# shield.net
KiCad netlist of a schematic drawn in EAGLE
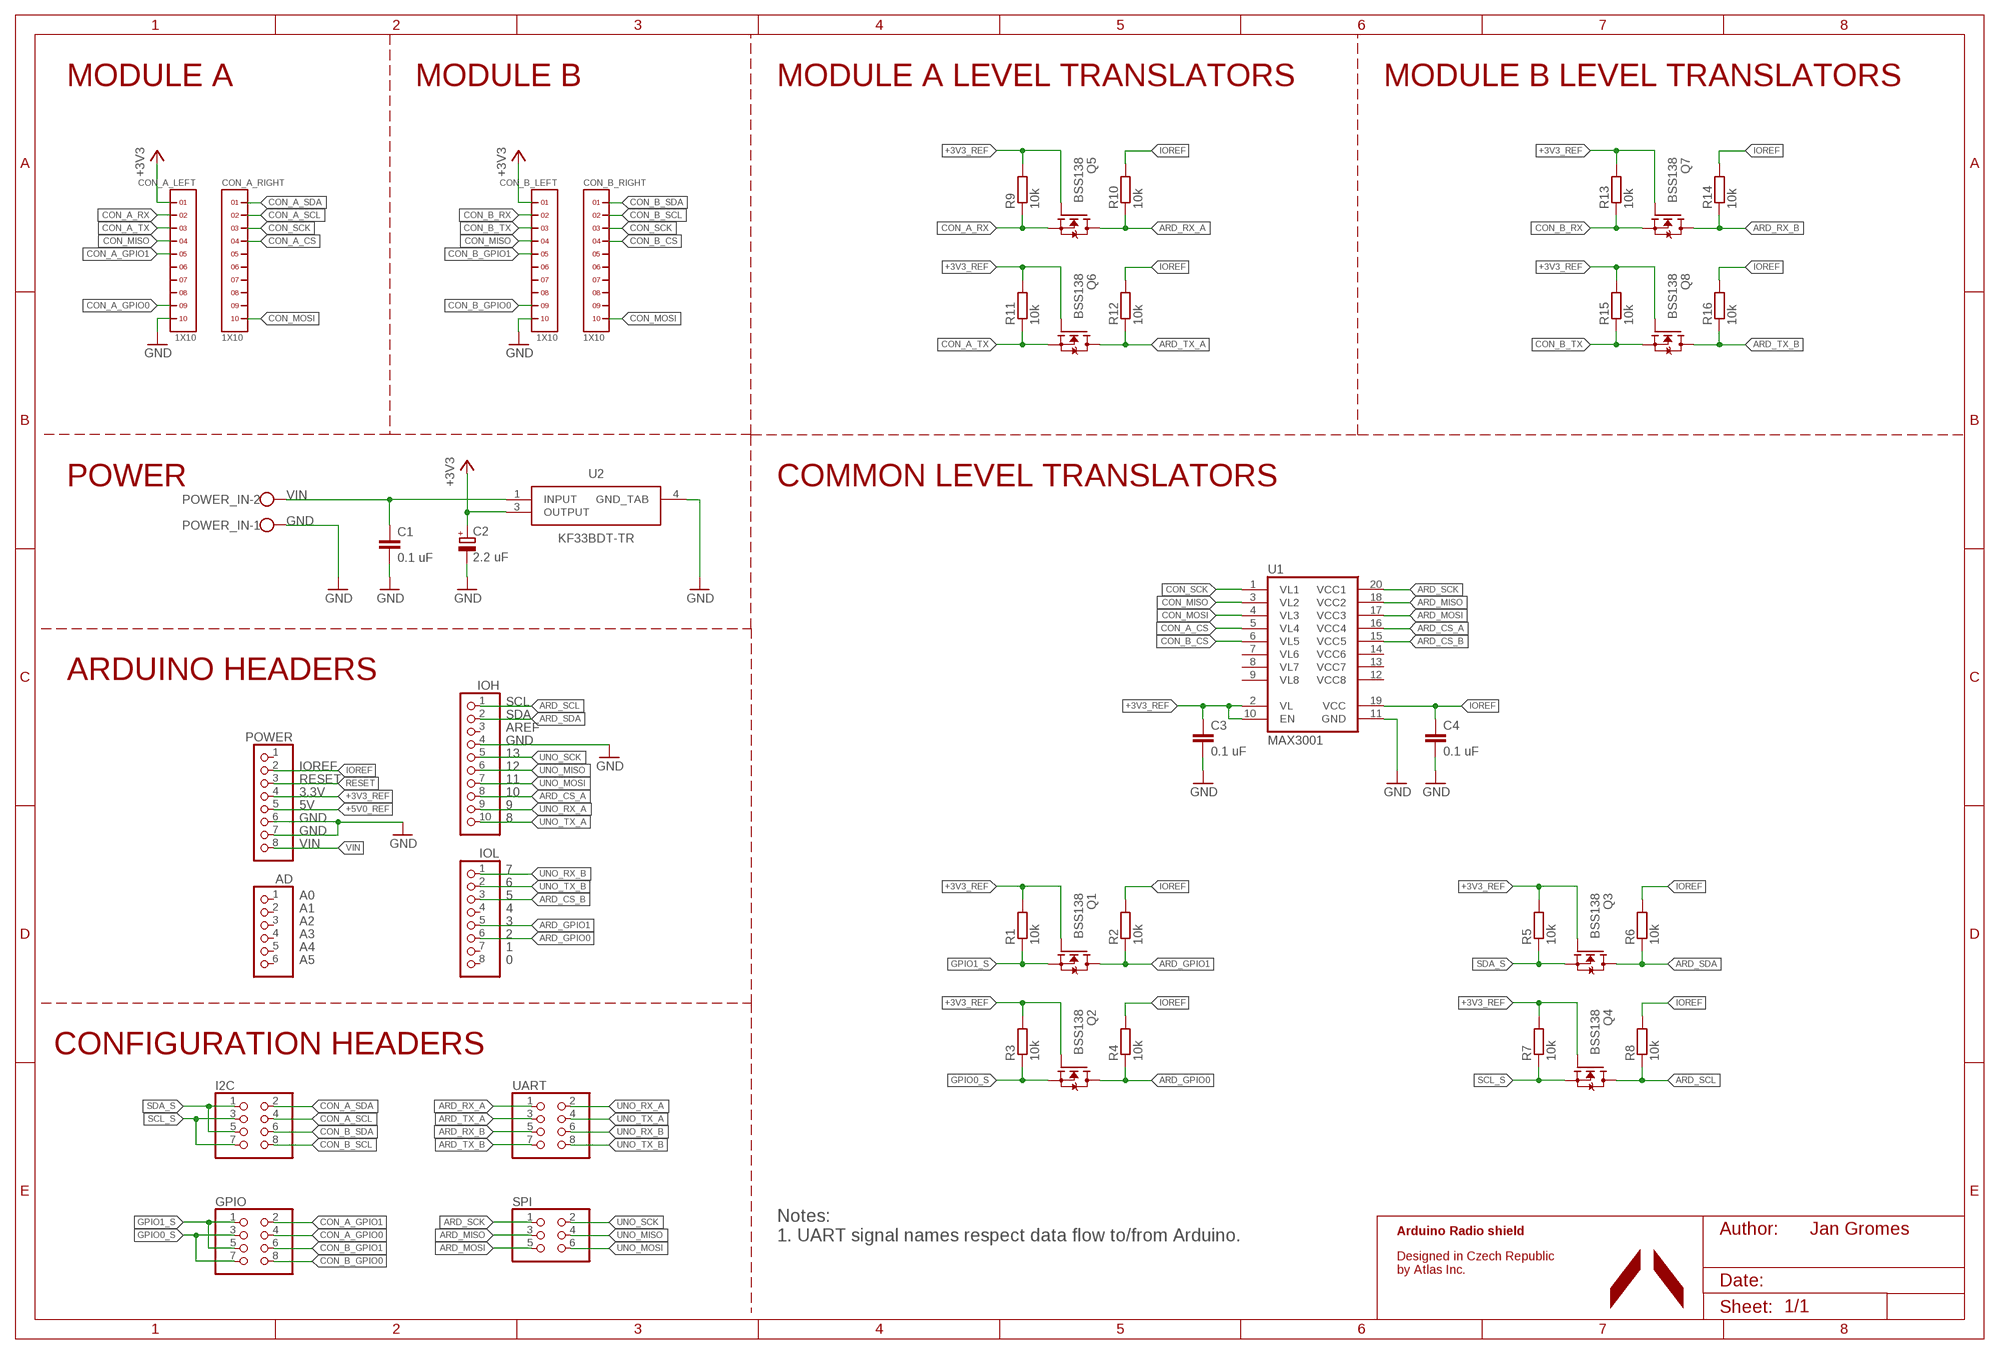
[diagram p0: schematic, sheet 1]

(export (version "E")
  (design (tool "Eeschema 10.0.6"))
  (components
    (comp (ref "AD")
      (value "PINHD-1X6")
      (footprint "eagle-import:1X06")
      (libsource (lib "eagle-import") (part "PINHD-1X6"))
    )
    (comp (ref "C1")
      (value "0.1 uF")
      (footprint "eagle-import:C0603")
      (libsource (lib "eagle-import") (part "C-EUC0603"))
    )
    (comp (ref "C2")
      (value "2.2 uF")
      (footprint "eagle-import:SMC_A")
      (libsource (lib "eagle-import") (part "CPOL-EUSMCA"))
    )
    (comp (ref "C3")
      (value "0.1 uF")
      (footprint "eagle-import:C0603")
      (libsource (lib "eagle-import") (part "C-EUC0603"))
    )
    (comp (ref "C4")
      (value "0.1 uF")
      (footprint "eagle-import:C0603")
      (libsource (lib "eagle-import") (part "C-EUC0603"))
    )
    (comp (ref "CON_A_LEFT")
      (value "1X10")
      (footprint "eagle-import:1X10")
      (libsource (lib "eagle-import") (part "1X10"))
    )
    (comp (ref "CON_A_RIGHT")
      (value "1X10")
      (footprint "eagle-import:1X10")
      (libsource (lib "eagle-import") (part "1X10"))
    )
    (comp (ref "CON_B_LEFT")
      (value "1X10")
      (footprint "eagle-import:1X10")
      (libsource (lib "eagle-import") (part "1X10"))
    )
    (comp (ref "CON_B_RIGHT")
      (value "1X10")
      (footprint "eagle-import:1X10")
      (libsource (lib "eagle-import") (part "1X10"))
    )
    (comp (ref "GPIO")
      (value "PINHD-2X4")
      (footprint "eagle-import:2X04")
      (libsource (lib "eagle-import") (part "PINHD-2X4"))
    )
    (comp (ref "I2C")
      (value "PINHD-2X4")
      (footprint "eagle-import:2X04")
      (libsource (lib "eagle-import") (part "PINHD-2X4"))
    )
    (comp (ref "IOH")
      (value "PINHD-1X10")
      (footprint "eagle-import:1X10")
      (libsource (lib "eagle-import") (part "PINHD-1X10"))
    )
    (comp (ref "IOL")
      (value "PINHD-1X8")
      (footprint "eagle-import:1X08")
      (libsource (lib "eagle-import") (part "PINHD-1X8"))
    )
    (comp (ref "POWER")
      (value "PINHD-1X8")
      (footprint "eagle-import:1X08")
      (libsource (lib "eagle-import") (part "PINHD-1X8"))
    )
    (comp (ref "POWER_IN")
      (value "W237-102")
      (footprint "eagle-import:W237-102")
      (fields (field (name "MPN") "237-102"))
      (libsource (lib "eagle-import") (part "W237-102"))
    )
    (comp (ref "Q1")
      (value "BSS138")
      (footprint "eagle-import:SOT23")
      (fields (field (name "MF") "Fairchild"))
      (libsource (lib "eagle-import") (part "BSS138"))
    )
    (comp (ref "Q2")
      (value "BSS138")
      (footprint "eagle-import:SOT23")
      (fields (field (name "MF") "Fairchild"))
      (libsource (lib "eagle-import") (part "BSS138"))
    )
    (comp (ref "Q3")
      (value "BSS138")
      (footprint "eagle-import:SOT23")
      (fields (field (name "MF") "Fairchild"))
      (libsource (lib "eagle-import") (part "BSS138"))
    )
    (comp (ref "Q4")
      (value "BSS138")
      (footprint "eagle-import:SOT23")
      (fields (field (name "MF") "Fairchild"))
      (libsource (lib "eagle-import") (part "BSS138"))
    )
    (comp (ref "Q5")
      (value "BSS138")
      (footprint "eagle-import:SOT23")
      (fields (field (name "MF") "Fairchild"))
      (libsource (lib "eagle-import") (part "BSS138"))
    )
    (comp (ref "Q6")
      (value "BSS138")
      (footprint "eagle-import:SOT23")
      (fields (field (name "MF") "Fairchild"))
      (libsource (lib "eagle-import") (part "BSS138"))
    )
    (comp (ref "Q7")
      (value "BSS138")
      (footprint "eagle-import:SOT23")
      (fields (field (name "MF") "Fairchild"))
      (libsource (lib "eagle-import") (part "BSS138"))
    )
    (comp (ref "Q8")
      (value "BSS138")
      (footprint "eagle-import:SOT23")
      (fields (field (name "MF") "Fairchild"))
      (libsource (lib "eagle-import") (part "BSS138"))
    )
    (comp (ref "R1")
      (value "10k")
      (footprint "eagle-import:R0603")
      (libsource (lib "eagle-import") (part "R-EU_R0603"))
    )
    (comp (ref "R2")
      (value "10k")
      (footprint "eagle-import:R0603")
      (libsource (lib "eagle-import") (part "R-EU_R0603"))
    )
    (comp (ref "R3")
      (value "10k")
      (footprint "eagle-import:R0603")
      (libsource (lib "eagle-import") (part "R-EU_R0603"))
    )
    (comp (ref "R4")
      (value "10k")
      (footprint "eagle-import:R0603")
      (libsource (lib "eagle-import") (part "R-EU_R0603"))
    )
    (comp (ref "R5")
      (value "10k")
      (footprint "eagle-import:R0603")
      (libsource (lib "eagle-import") (part "R-EU_R0603"))
    )
    (comp (ref "R6")
      (value "10k")
      (footprint "eagle-import:R0603")
      (libsource (lib "eagle-import") (part "R-EU_R0603"))
    )
    (comp (ref "R7")
      (value "10k")
      (footprint "eagle-import:R0603")
      (libsource (lib "eagle-import") (part "R-EU_R0603"))
    )
    (comp (ref "R8")
      (value "10k")
      (footprint "eagle-import:R0603")
      (libsource (lib "eagle-import") (part "R-EU_R0603"))
    )
    (comp (ref "R9")
      (value "10k")
      (footprint "eagle-import:R0603")
      (libsource (lib "eagle-import") (part "R-EU_R0603"))
    )
    (comp (ref "R10")
      (value "10k")
      (footprint "eagle-import:R0603")
      (libsource (lib "eagle-import") (part "R-EU_R0603"))
    )
    (comp (ref "R11")
      (value "10k")
      (footprint "eagle-import:R0603")
      (libsource (lib "eagle-import") (part "R-EU_R0603"))
    )
    (comp (ref "R12")
      (value "10k")
      (footprint "eagle-import:R0603")
      (libsource (lib "eagle-import") (part "R-EU_R0603"))
    )
    (comp (ref "R13")
      (value "10k")
      (footprint "eagle-import:R0603")
      (libsource (lib "eagle-import") (part "R-EU_R0603"))
    )
    (comp (ref "R14")
      (value "10k")
      (footprint "eagle-import:R0603")
      (libsource (lib "eagle-import") (part "R-EU_R0603"))
    )
    (comp (ref "R15")
      (value "10k")
      (footprint "eagle-import:R0603")
      (libsource (lib "eagle-import") (part "R-EU_R0603"))
    )
    (comp (ref "R16")
      (value "10k")
      (footprint "eagle-import:R0603")
      (libsource (lib "eagle-import") (part "R-EU_R0603"))
    )
    (comp (ref "SPI")
      (value "PINHD-2X3")
      (footprint "eagle-import:2X03")
      (libsource (lib "eagle-import") (part "PINHD-2X3"))
    )
    (comp (ref "U1")
      (value "MAX3001")
      (footprint "eagle-import:TSSOP20")
      (libsource (lib "eagle-import") (part "MAX3001"))
    )
    (comp (ref "U2")
      (value "KF33BDT-TR")
      (footprint "eagle-import:TO228P972X240-3N")
      (fields (field (name "RS_PART_NUMBER") "7140616"))
      (libsource (lib "eagle-import") (part "KF33BDT-TR"))
    )
    (comp (ref "UART")
      (value "PINHD-2X4")
      (footprint "eagle-import:2X04")
      (libsource (lib "eagle-import") (part "PINHD-2X4"))
    )
  )
  (nets
    (net (code "1") (name "+3V3") (class "Default")
      (node (ref "C2") (pin "+") (pinfunction "+_+") (pintype "passive"))
      (node (ref "CON_A_LEFT") (pin "1") (pinfunction "1_1") (pintype "bidirectional"))
      (node (ref "CON_B_LEFT") (pin "1") (pinfunction "1_1") (pintype "bidirectional"))
      (node (ref "U2") (pin "3") (pinfunction "OUTPUT_3") (pintype "output"))
    )
    (net (code "2") (name "+3V3_REF") (class "Default")
      (node (ref "C3") (pin "1") (pinfunction "1_1") (pintype "passive"))
      (node (ref "POWER") (pin "4") (pinfunction "4_4") (pintype "passive"))
      (node (ref "Q1") (pin "1") (pinfunction "G_1") (pintype "passive"))
      (node (ref "Q2") (pin "1") (pinfunction "G_1") (pintype "passive"))
      (node (ref "Q3") (pin "1") (pinfunction "G_1") (pintype "passive"))
      (node (ref "Q4") (pin "1") (pinfunction "G_1") (pintype "passive"))
      (node (ref "Q5") (pin "1") (pinfunction "G_1") (pintype "passive"))
      (node (ref "Q6") (pin "1") (pinfunction "G_1") (pintype "passive"))
      (node (ref "Q7") (pin "1") (pinfunction "G_1") (pintype "passive"))
      (node (ref "Q8") (pin "1") (pinfunction "G_1") (pintype "passive"))
      (node (ref "R1") (pin "2") (pinfunction "2_2") (pintype "passive"))
      (node (ref "R11") (pin "2") (pinfunction "2_2") (pintype "passive"))
      (node (ref "R13") (pin "2") (pinfunction "2_2") (pintype "passive"))
      (node (ref "R15") (pin "2") (pinfunction "2_2") (pintype "passive"))
      (node (ref "R3") (pin "2") (pinfunction "2_2") (pintype "passive"))
      (node (ref "R5") (pin "2") (pinfunction "2_2") (pintype "passive"))
      (node (ref "R7") (pin "2") (pinfunction "2_2") (pintype "passive"))
      (node (ref "R9") (pin "2") (pinfunction "2_2") (pintype "passive"))
      (node (ref "U1") (pin "10") (pinfunction "EN_10") (pintype "power_in"))
      (node (ref "U1") (pin "2") (pinfunction "VL_2") (pintype "input"))
    )
    (net (code "3") (name "+5V0_REF") (class "Default")
      (node (ref "POWER") (pin "5") (pinfunction "5_5") (pintype "passive"))
    )
    (net (code "4") (name "ARD_CS_A") (class "Default")
      (node (ref "IOH") (pin "8") (pinfunction "8_8") (pintype "passive"))
      (node (ref "U1") (pin "16") (pinfunction "VCC4_16") (pintype "bidirectional"))
    )
    (net (code "5") (name "ARD_CS_B") (class "Default")
      (node (ref "IOL") (pin "3") (pinfunction "3_3") (pintype "passive"))
      (node (ref "U1") (pin "15") (pinfunction "VCC5_15") (pintype "bidirectional"))
    )
    (net (code "6") (name "ARD_GPIO0") (class "Default")
      (node (ref "IOL") (pin "6") (pinfunction "6_6") (pintype "passive"))
      (node (ref "Q2") (pin "3") (pinfunction "D_3") (pintype "passive"))
      (node (ref "R4") (pin "1") (pinfunction "1_1") (pintype "passive"))
    )
    (net (code "7") (name "ARD_GPIO1") (class "Default")
      (node (ref "IOL") (pin "5") (pinfunction "5_5") (pintype "passive"))
      (node (ref "Q1") (pin "3") (pinfunction "D_3") (pintype "passive"))
      (node (ref "R2") (pin "1") (pinfunction "1_1") (pintype "passive"))
    )
    (net (code "8") (name "ARD_MISO") (class "Default")
      (node (ref "SPI") (pin "3") (pinfunction "3_3") (pintype "passive"))
      (node (ref "U1") (pin "18") (pinfunction "VCC2_18") (pintype "bidirectional"))
    )
    (net (code "9") (name "ARD_MOSI") (class "Default")
      (node (ref "SPI") (pin "5") (pinfunction "5_5") (pintype "passive"))
      (node (ref "U1") (pin "17") (pinfunction "VCC3_17") (pintype "bidirectional"))
    )
    (net (code "10") (name "ARD_RX_A") (class "Default")
      (node (ref "Q5") (pin "3") (pinfunction "D_3") (pintype "passive"))
      (node (ref "R10") (pin "1") (pinfunction "1_1") (pintype "passive"))
      (node (ref "UART") (pin "1") (pinfunction "1_1") (pintype "passive"))
    )
    (net (code "11") (name "ARD_RX_B") (class "Default")
      (node (ref "Q7") (pin "3") (pinfunction "D_3") (pintype "passive"))
      (node (ref "R14") (pin "1") (pinfunction "1_1") (pintype "passive"))
      (node (ref "UART") (pin "5") (pinfunction "5_5") (pintype "passive"))
    )
    (net (code "12") (name "ARD_SCK") (class "Default")
      (node (ref "SPI") (pin "1") (pinfunction "1_1") (pintype "passive"))
      (node (ref "U1") (pin "20") (pinfunction "VCC1_20") (pintype "bidirectional"))
    )
    (net (code "13") (name "ARD_SCL") (class "Default")
      (node (ref "IOH") (pin "1") (pinfunction "1_1") (pintype "passive"))
      (node (ref "Q4") (pin "3") (pinfunction "D_3") (pintype "passive"))
      (node (ref "R8") (pin "1") (pinfunction "1_1") (pintype "passive"))
    )
    (net (code "14") (name "ARD_SDA") (class "Default")
      (node (ref "IOH") (pin "2") (pinfunction "2_2") (pintype "passive"))
      (node (ref "Q3") (pin "3") (pinfunction "D_3") (pintype "passive"))
      (node (ref "R6") (pin "1") (pinfunction "1_1") (pintype "passive"))
    )
    (net (code "15") (name "ARD_TX_A") (class "Default")
      (node (ref "Q6") (pin "3") (pinfunction "D_3") (pintype "passive"))
      (node (ref "R12") (pin "1") (pinfunction "1_1") (pintype "passive"))
      (node (ref "UART") (pin "3") (pinfunction "3_3") (pintype "passive"))
    )
    (net (code "16") (name "ARD_TX_B") (class "Default")
      (node (ref "Q8") (pin "3") (pinfunction "D_3") (pintype "passive"))
      (node (ref "R16") (pin "1") (pinfunction "1_1") (pintype "passive"))
      (node (ref "UART") (pin "7") (pinfunction "7_7") (pintype "passive"))
    )
    (net (code "17") (name "CON_A_CS") (class "Default")
      (node (ref "CON_A_RIGHT") (pin "4") (pinfunction "4_4") (pintype "bidirectional"))
      (node (ref "U1") (pin "5") (pinfunction "VL4_5") (pintype "bidirectional"))
    )
    (net (code "18") (name "CON_A_GPIO0") (class "Default")
      (node (ref "CON_A_LEFT") (pin "9") (pinfunction "9_9") (pintype "bidirectional"))
      (node (ref "GPIO") (pin "4") (pinfunction "4_4") (pintype "passive"))
    )
    (net (code "19") (name "CON_A_GPIO1") (class "Default")
      (node (ref "CON_A_LEFT") (pin "5") (pinfunction "5_5") (pintype "bidirectional"))
      (node (ref "GPIO") (pin "2") (pinfunction "2_2") (pintype "passive"))
    )
    (net (code "20") (name "CON_A_RX") (class "Default")
      (node (ref "CON_A_LEFT") (pin "2") (pinfunction "2_2") (pintype "bidirectional"))
      (node (ref "Q5") (pin "2") (pinfunction "S_2") (pintype "passive"))
      (node (ref "R9") (pin "1") (pinfunction "1_1") (pintype "passive"))
    )
    (net (code "21") (name "CON_A_SCL") (class "Default")
      (node (ref "CON_A_RIGHT") (pin "2") (pinfunction "2_2") (pintype "bidirectional"))
      (node (ref "I2C") (pin "4") (pinfunction "4_4") (pintype "passive"))
    )
    (net (code "22") (name "CON_A_SDA") (class "Default")
      (node (ref "CON_A_RIGHT") (pin "1") (pinfunction "1_1") (pintype "bidirectional"))
      (node (ref "I2C") (pin "2") (pinfunction "2_2") (pintype "passive"))
    )
    (net (code "23") (name "CON_A_TX") (class "Default")
      (node (ref "CON_A_LEFT") (pin "3") (pinfunction "3_3") (pintype "bidirectional"))
      (node (ref "Q6") (pin "2") (pinfunction "S_2") (pintype "passive"))
      (node (ref "R11") (pin "1") (pinfunction "1_1") (pintype "passive"))
    )
    (net (code "24") (name "CON_B_CS") (class "Default")
      (node (ref "CON_B_RIGHT") (pin "4") (pinfunction "4_4") (pintype "bidirectional"))
      (node (ref "U1") (pin "6") (pinfunction "VL5_6") (pintype "bidirectional"))
    )
    (net (code "25") (name "CON_B_GPIO0") (class "Default")
      (node (ref "CON_B_LEFT") (pin "9") (pinfunction "9_9") (pintype "bidirectional"))
      (node (ref "GPIO") (pin "8") (pinfunction "8_8") (pintype "passive"))
    )
    (net (code "26") (name "CON_B_GPIO1") (class "Default")
      (node (ref "CON_B_LEFT") (pin "5") (pinfunction "5_5") (pintype "bidirectional"))
      (node (ref "GPIO") (pin "6") (pinfunction "6_6") (pintype "passive"))
    )
    (net (code "27") (name "CON_B_RX") (class "Default")
      (node (ref "CON_B_LEFT") (pin "2") (pinfunction "2_2") (pintype "bidirectional"))
      (node (ref "Q7") (pin "2") (pinfunction "S_2") (pintype "passive"))
      (node (ref "R13") (pin "1") (pinfunction "1_1") (pintype "passive"))
    )
    (net (code "28") (name "CON_B_SCL") (class "Default")
      (node (ref "CON_B_RIGHT") (pin "2") (pinfunction "2_2") (pintype "bidirectional"))
      (node (ref "I2C") (pin "8") (pinfunction "8_8") (pintype "passive"))
    )
    (net (code "29") (name "CON_B_SDA") (class "Default")
      (node (ref "CON_B_RIGHT") (pin "1") (pinfunction "1_1") (pintype "bidirectional"))
      (node (ref "I2C") (pin "6") (pinfunction "6_6") (pintype "passive"))
    )
    (net (code "30") (name "CON_B_TX") (class "Default")
      (node (ref "CON_B_LEFT") (pin "3") (pinfunction "3_3") (pintype "bidirectional"))
      (node (ref "Q8") (pin "2") (pinfunction "S_2") (pintype "passive"))
      (node (ref "R15") (pin "1") (pinfunction "1_1") (pintype "passive"))
    )
    (net (code "31") (name "CON_MISO") (class "Default")
      (node (ref "CON_A_LEFT") (pin "4") (pinfunction "4_4") (pintype "bidirectional"))
      (node (ref "CON_B_LEFT") (pin "4") (pinfunction "4_4") (pintype "bidirectional"))
      (node (ref "U1") (pin "3") (pinfunction "VL2_3") (pintype "bidirectional"))
    )
    (net (code "32") (name "CON_MOSI") (class "Default")
      (node (ref "CON_A_RIGHT") (pin "10") (pinfunction "10_10") (pintype "bidirectional"))
      (node (ref "CON_B_RIGHT") (pin "10") (pinfunction "10_10") (pintype "bidirectional"))
      (node (ref "U1") (pin "4") (pinfunction "VL3_4") (pintype "bidirectional"))
    )
    (net (code "33") (name "CON_SCK") (class "Default")
      (node (ref "CON_A_RIGHT") (pin "3") (pinfunction "3_3") (pintype "bidirectional"))
      (node (ref "CON_B_RIGHT") (pin "3") (pinfunction "3_3") (pintype "bidirectional"))
      (node (ref "U1") (pin "1") (pinfunction "VL1_1") (pintype "bidirectional"))
    )
    (net (code "34") (name "GND") (class "Default")
      (node (ref "C1") (pin "2") (pinfunction "2_2") (pintype "passive"))
      (node (ref "C2") (pin "-") (pinfunction "-_-") (pintype "passive"))
      (node (ref "C3") (pin "2") (pinfunction "2_2") (pintype "passive"))
      (node (ref "C4") (pin "2") (pinfunction "2_2") (pintype "passive"))
      (node (ref "CON_A_LEFT") (pin "10") (pinfunction "10_10") (pintype "bidirectional"))
      (node (ref "CON_B_LEFT") (pin "10") (pinfunction "10_10") (pintype "bidirectional"))
      (node (ref "IOH") (pin "4") (pinfunction "4_4") (pintype "passive"))
      (node (ref "POWER") (pin "6") (pinfunction "6_6") (pintype "passive"))
      (node (ref "POWER") (pin "7") (pinfunction "7_7") (pintype "passive"))
      (node (ref "POWER_IN") (pin "1") (pinfunction "KL_1") (pintype "passive"))
      (node (ref "U1") (pin "11") (pinfunction "GND_11") (pintype "power_in"))
      (node (ref "U2") (pin "4") (pinfunction "GND_TAB_4") (pintype "power_in"))
    )
    (net (code "35") (name "GPIO0_S") (class "Default")
      (node (ref "GPIO") (pin "3") (pinfunction "3_3") (pintype "passive"))
      (node (ref "GPIO") (pin "7") (pinfunction "7_7") (pintype "passive"))
      (node (ref "Q2") (pin "2") (pinfunction "S_2") (pintype "passive"))
      (node (ref "R3") (pin "1") (pinfunction "1_1") (pintype "passive"))
    )
    (net (code "36") (name "GPIO1_S") (class "Default")
      (node (ref "GPIO") (pin "1") (pinfunction "1_1") (pintype "passive"))
      (node (ref "GPIO") (pin "5") (pinfunction "5_5") (pintype "passive"))
      (node (ref "Q1") (pin "2") (pinfunction "S_2") (pintype "passive"))
      (node (ref "R1") (pin "1") (pinfunction "1_1") (pintype "passive"))
    )
    (net (code "37") (name "IOREF") (class "Default")
      (node (ref "C4") (pin "1") (pinfunction "1_1") (pintype "passive"))
      (node (ref "POWER") (pin "2") (pinfunction "2_2") (pintype "passive"))
      (node (ref "R10") (pin "2") (pinfunction "2_2") (pintype "passive"))
      (node (ref "R12") (pin "2") (pinfunction "2_2") (pintype "passive"))
      (node (ref "R14") (pin "2") (pinfunction "2_2") (pintype "passive"))
      (node (ref "R16") (pin "2") (pinfunction "2_2") (pintype "passive"))
      (node (ref "R2") (pin "2") (pinfunction "2_2") (pintype "passive"))
      (node (ref "R4") (pin "2") (pinfunction "2_2") (pintype "passive"))
      (node (ref "R6") (pin "2") (pinfunction "2_2") (pintype "passive"))
      (node (ref "R8") (pin "2") (pinfunction "2_2") (pintype "passive"))
      (node (ref "U1") (pin "19") (pinfunction "VCC_19") (pintype "power_in"))
    )
    (net (code "38") (name "RESET") (class "Default")
      (node (ref "POWER") (pin "3") (pinfunction "3_3") (pintype "passive"))
    )
    (net (code "39") (name "SCL_S") (class "Default")
      (node (ref "I2C") (pin "3") (pinfunction "3_3") (pintype "passive"))
      (node (ref "I2C") (pin "7") (pinfunction "7_7") (pintype "passive"))
      (node (ref "Q4") (pin "2") (pinfunction "S_2") (pintype "passive"))
      (node (ref "R7") (pin "1") (pinfunction "1_1") (pintype "passive"))
    )
    (net (code "40") (name "SDA_S") (class "Default")
      (node (ref "I2C") (pin "1") (pinfunction "1_1") (pintype "passive"))
      (node (ref "I2C") (pin "5") (pinfunction "5_5") (pintype "passive"))
      (node (ref "Q3") (pin "2") (pinfunction "S_2") (pintype "passive"))
      (node (ref "R5") (pin "1") (pinfunction "1_1") (pintype "passive"))
    )
    (net (code "41") (name "UNO_MISO") (class "Default")
      (node (ref "IOH") (pin "6") (pinfunction "6_6") (pintype "passive"))
      (node (ref "SPI") (pin "4") (pinfunction "4_4") (pintype "passive"))
    )
    (net (code "42") (name "UNO_MOSI") (class "Default")
      (node (ref "IOH") (pin "7") (pinfunction "7_7") (pintype "passive"))
      (node (ref "SPI") (pin "6") (pinfunction "6_6") (pintype "passive"))
    )
    (net (code "43") (name "UNO_RX_A") (class "Default")
      (node (ref "IOH") (pin "9") (pinfunction "9_9") (pintype "passive"))
      (node (ref "UART") (pin "2") (pinfunction "2_2") (pintype "passive"))
    )
    (net (code "44") (name "UNO_RX_B") (class "Default")
      (node (ref "IOL") (pin "1") (pinfunction "1_1") (pintype "passive"))
      (node (ref "UART") (pin "6") (pinfunction "6_6") (pintype "passive"))
    )
    (net (code "45") (name "UNO_SCK") (class "Default")
      (node (ref "IOH") (pin "5") (pinfunction "5_5") (pintype "passive"))
      (node (ref "SPI") (pin "2") (pinfunction "2_2") (pintype "passive"))
    )
    (net (code "46") (name "UNO_TX_A") (class "Default")
      (node (ref "IOH") (pin "10") (pinfunction "10_10") (pintype "passive"))
      (node (ref "UART") (pin "4") (pinfunction "4_4") (pintype "passive"))
    )
    (net (code "47") (name "UNO_TX_B") (class "Default")
      (node (ref "IOL") (pin "2") (pinfunction "2_2") (pintype "passive"))
      (node (ref "UART") (pin "8") (pinfunction "8_8") (pintype "passive"))
    )
    (net (code "48") (name "VIN") (class "Default")
      (node (ref "C1") (pin "1") (pinfunction "1_1") (pintype "passive"))
      (node (ref "POWER") (pin "8") (pinfunction "8_8") (pintype "passive"))
      (node (ref "POWER_IN") (pin "2") (pinfunction "KL_2") (pintype "passive"))
      (node (ref "U2") (pin "1") (pinfunction "INPUT_1") (pintype "input"))
    )
    (net (code "49") (name "unconnected-(AD-Pad1)") (class "Default")
      (node (ref "AD") (pin "1") (pinfunction "1_1") (pintype "passive"))
    )
    (net (code "50") (name "unconnected-(AD-Pad2)") (class "Default")
      (node (ref "AD") (pin "2") (pinfunction "2_2") (pintype "passive"))
    )
    (net (code "51") (name "unconnected-(AD-Pad3)") (class "Default")
      (node (ref "AD") (pin "3") (pinfunction "3_3") (pintype "passive"))
    )
    (net (code "52") (name "unconnected-(AD-Pad4)") (class "Default")
      (node (ref "AD") (pin "4") (pinfunction "4_4") (pintype "passive"))
    )
    (net (code "53") (name "unconnected-(AD-Pad5)") (class "Default")
      (node (ref "AD") (pin "5") (pinfunction "5_5") (pintype "passive"))
    )
    (net (code "54") (name "unconnected-(AD-Pad6)") (class "Default")
      (node (ref "AD") (pin "6") (pinfunction "6_6") (pintype "passive"))
    )
    (net (code "55") (name "unconnected-(CON_A_LEFT-Pad6)") (class "Default")
      (node (ref "CON_A_LEFT") (pin "6") (pinfunction "6_6") (pintype "bidirectional"))
    )
    (net (code "56") (name "unconnected-(CON_A_LEFT-Pad7)") (class "Default")
      (node (ref "CON_A_LEFT") (pin "7") (pinfunction "7_7") (pintype "bidirectional"))
    )
    (net (code "57") (name "unconnected-(CON_A_LEFT-Pad8)") (class "Default")
      (node (ref "CON_A_LEFT") (pin "8") (pinfunction "8_8") (pintype "bidirectional"))
    )
    (net (code "58") (name "unconnected-(CON_A_RIGHT-Pad5)") (class "Default")
      (node (ref "CON_A_RIGHT") (pin "5") (pinfunction "5_5") (pintype "bidirectional"))
    )
    (net (code "59") (name "unconnected-(CON_A_RIGHT-Pad6)") (class "Default")
      (node (ref "CON_A_RIGHT") (pin "6") (pinfunction "6_6") (pintype "bidirectional"))
    )
    (net (code "60") (name "unconnected-(CON_A_RIGHT-Pad7)") (class "Default")
      (node (ref "CON_A_RIGHT") (pin "7") (pinfunction "7_7") (pintype "bidirectional"))
    )
    (net (code "61") (name "unconnected-(CON_A_RIGHT-Pad8)") (class "Default")
      (node (ref "CON_A_RIGHT") (pin "8") (pinfunction "8_8") (pintype "bidirectional"))
    )
    (net (code "62") (name "unconnected-(CON_A_RIGHT-Pad9)") (class "Default")
      (node (ref "CON_A_RIGHT") (pin "9") (pinfunction "9_9") (pintype "bidirectional"))
    )
    (net (code "63") (name "unconnected-(CON_B_LEFT-Pad6)") (class "Default")
      (node (ref "CON_B_LEFT") (pin "6") (pinfunction "6_6") (pintype "bidirectional"))
    )
    (net (code "64") (name "unconnected-(CON_B_LEFT-Pad7)") (class "Default")
      (node (ref "CON_B_LEFT") (pin "7") (pinfunction "7_7") (pintype "bidirectional"))
    )
    (net (code "65") (name "unconnected-(CON_B_LEFT-Pad8)") (class "Default")
      (node (ref "CON_B_LEFT") (pin "8") (pinfunction "8_8") (pintype "bidirectional"))
    )
    (net (code "66") (name "unconnected-(CON_B_RIGHT-Pad5)") (class "Default")
      (node (ref "CON_B_RIGHT") (pin "5") (pinfunction "5_5") (pintype "bidirectional"))
    )
    (net (code "67") (name "unconnected-(CON_B_RIGHT-Pad6)") (class "Default")
      (node (ref "CON_B_RIGHT") (pin "6") (pinfunction "6_6") (pintype "bidirectional"))
    )
    (net (code "68") (name "unconnected-(CON_B_RIGHT-Pad7)") (class "Default")
      (node (ref "CON_B_RIGHT") (pin "7") (pinfunction "7_7") (pintype "bidirectional"))
    )
    (net (code "69") (name "unconnected-(CON_B_RIGHT-Pad8)") (class "Default")
      (node (ref "CON_B_RIGHT") (pin "8") (pinfunction "8_8") (pintype "bidirectional"))
    )
    (net (code "70") (name "unconnected-(CON_B_RIGHT-Pad9)") (class "Default")
      (node (ref "CON_B_RIGHT") (pin "9") (pinfunction "9_9") (pintype "bidirectional"))
    )
    (net (code "71") (name "unconnected-(IOH-Pad3)") (class "Default")
      (node (ref "IOH") (pin "3") (pinfunction "3_3") (pintype "passive"))
    )
    (net (code "72") (name "unconnected-(IOL-Pad4)") (class "Default")
      (node (ref "IOL") (pin "4") (pinfunction "4_4") (pintype "passive"))
    )
    (net (code "73") (name "unconnected-(IOL-Pad7)") (class "Default")
      (node (ref "IOL") (pin "7") (pinfunction "7_7") (pintype "passive"))
    )
    (net (code "74") (name "unconnected-(IOL-Pad8)") (class "Default")
      (node (ref "IOL") (pin "8") (pinfunction "8_8") (pintype "passive"))
    )
    (net (code "75") (name "unconnected-(POWER-Pad1)") (class "Default")
      (node (ref "POWER") (pin "1") (pinfunction "1_1") (pintype "passive"))
    )
    (net (code "76") (name "unconnected-(U1-VCC6-Pad14)") (class "Default")
      (node (ref "U1") (pin "14") (pinfunction "VCC6_14") (pintype "bidirectional"))
    )
    (net (code "77") (name "unconnected-(U1-VCC7-Pad13)") (class "Default")
      (node (ref "U1") (pin "13") (pinfunction "VCC7_13") (pintype "bidirectional"))
    )
    (net (code "78") (name "unconnected-(U1-VCC8-Pad12)") (class "Default")
      (node (ref "U1") (pin "12") (pinfunction "VCC8_12") (pintype "bidirectional"))
    )
    (net (code "79") (name "unconnected-(U1-VL6-Pad7)") (class "Default")
      (node (ref "U1") (pin "7") (pinfunction "VL6_7") (pintype "bidirectional"))
    )
    (net (code "80") (name "unconnected-(U1-VL7-Pad8)") (class "Default")
      (node (ref "U1") (pin "8") (pinfunction "VL7_8") (pintype "bidirectional"))
    )
    (net (code "81") (name "unconnected-(U1-VL8-Pad9)") (class "Default")
      (node (ref "U1") (pin "9") (pinfunction "VL8_9") (pintype "bidirectional"))
    )
  )
)
